# Double.net
KiCad netlist of a schematic drawn in EAGLE
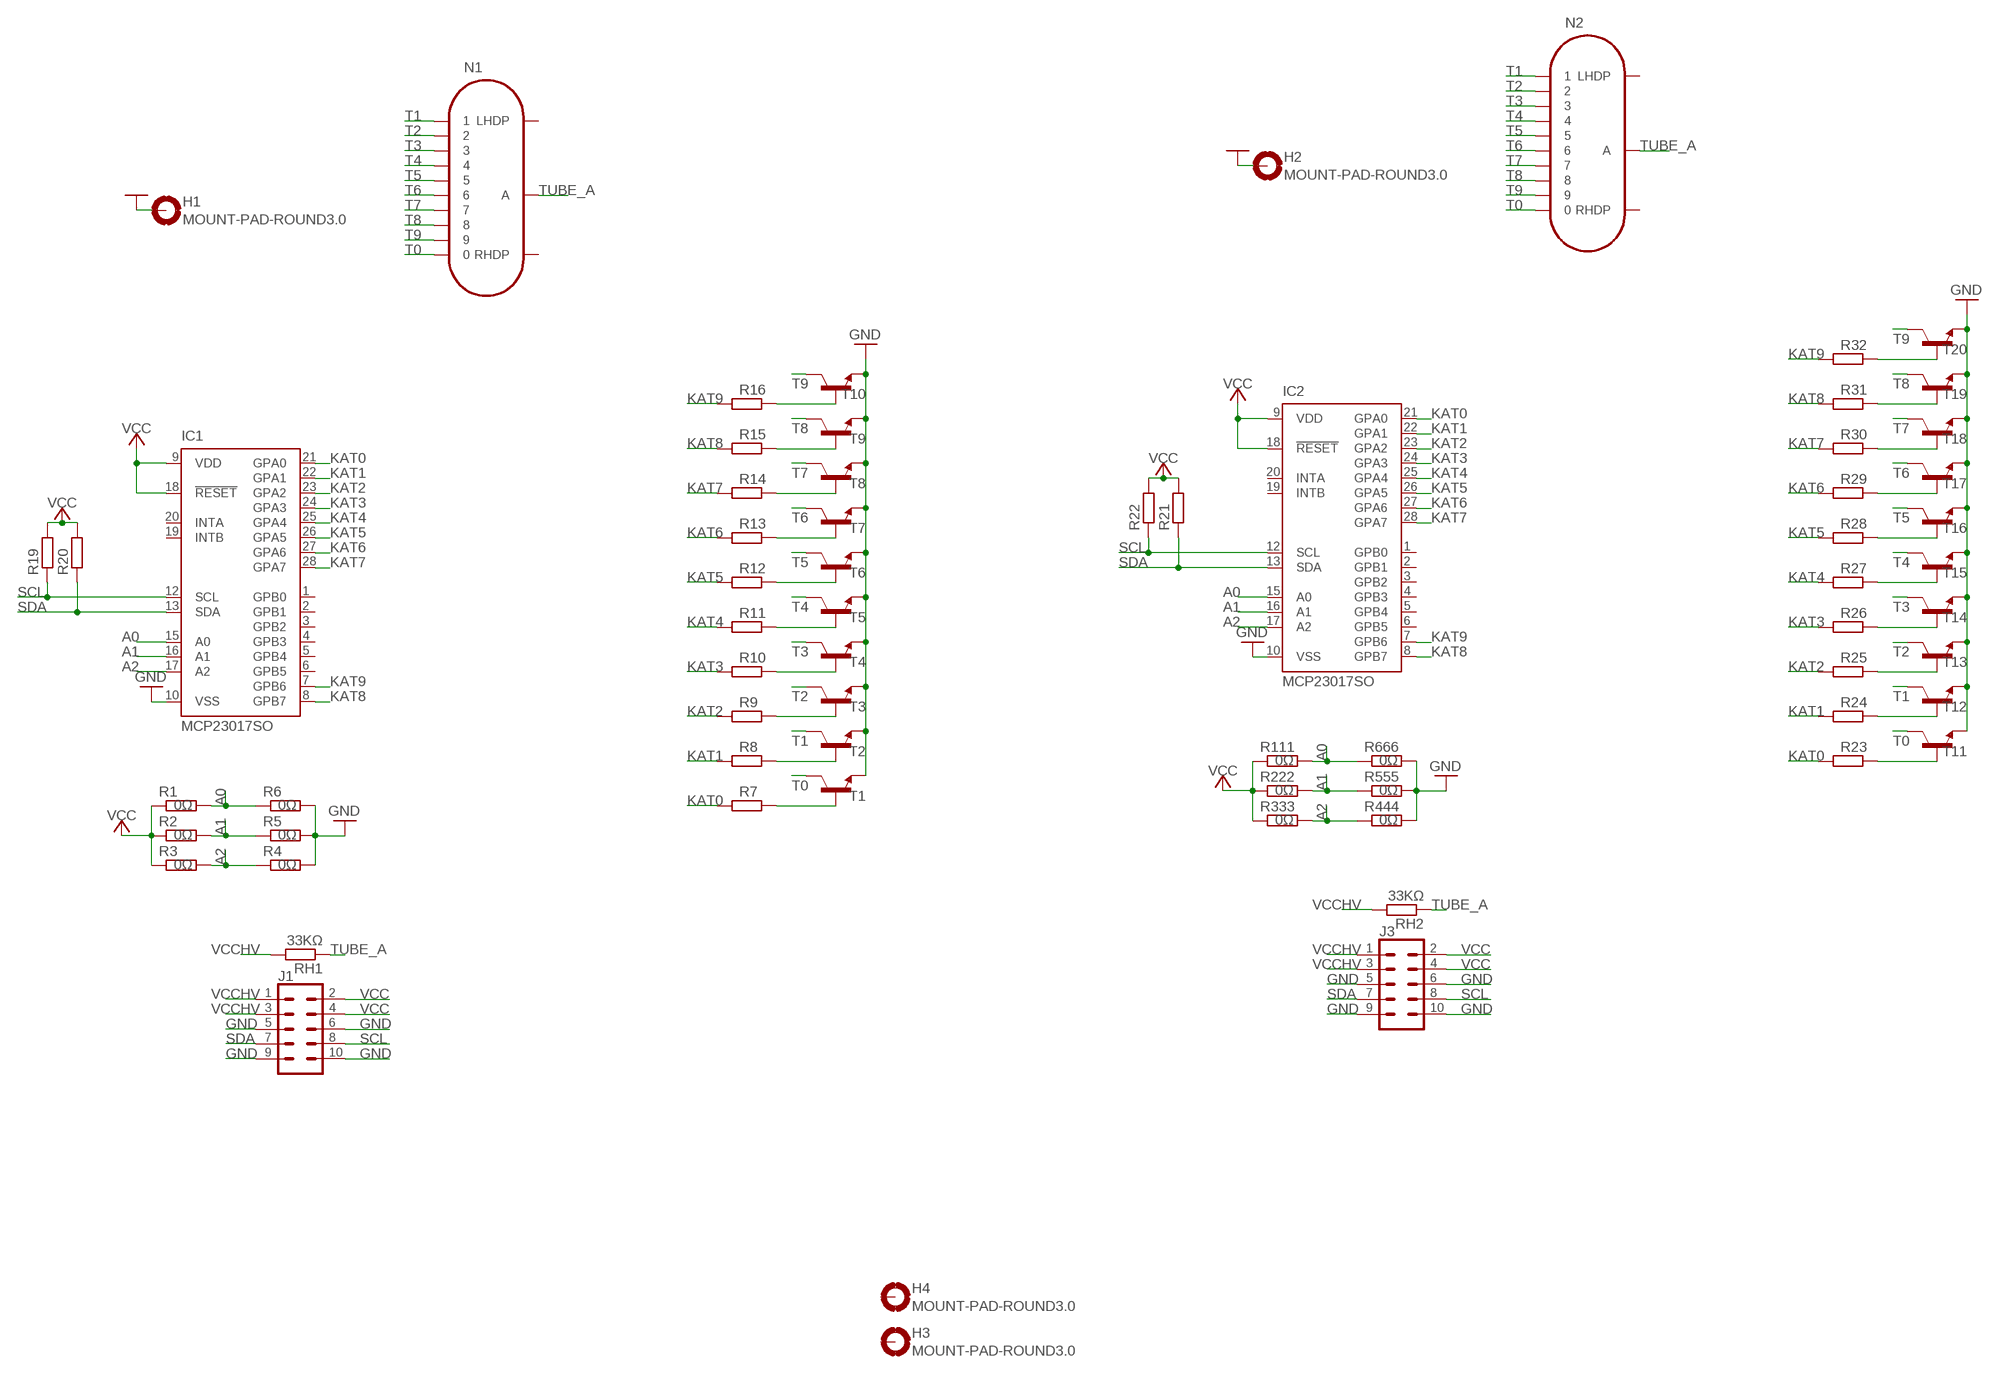
[diagram p0: schematic, sheet 1]

(export (version "E")
  (design (tool "Eeschema 10.0.6"))
  (components
    (comp (ref "H1")
      (value "MOUNT-PAD-ROUND3.0")
      (footprint "eagle-import:3,0-PAD")
      (libsource (lib "eagle-import") (part "MOUNT-PAD-ROUND3.0"))
    )
    (comp (ref "H2")
      (value "MOUNT-PAD-ROUND3.0")
      (footprint "eagle-import:3,0-PAD")
      (libsource (lib "eagle-import") (part "MOUNT-PAD-ROUND3.0"))
    )
    (comp (ref "H3")
      (value "MOUNT-PAD-ROUND3.0")
      (footprint "eagle-import:3,0-PAD")
      (libsource (lib "eagle-import") (part "MOUNT-PAD-ROUND3.0"))
    )
    (comp (ref "H4")
      (value "MOUNT-PAD-ROUND3.0")
      (footprint "eagle-import:3,0-PAD")
      (libsource (lib "eagle-import") (part "MOUNT-PAD-ROUND3.0"))
    )
    (comp (ref "IC1")
      (value "MCP23017SO")
      (footprint "eagle-import:SO28W")
      (libsource (lib "eagle-import") (part "MCP23017SO"))
    )
    (comp (ref "IC2")
      (value "MCP23017SO")
      (footprint "eagle-import:SO28W")
      (libsource (lib "eagle-import") (part "MCP23017SO"))
    )
    (comp (ref "J1")
      (value "CONN_05X2PTH")
      (footprint "eagle-import:2X5")
      (libsource (lib "eagle-import") (part "CONN_05X2PTH"))
    )
    (comp (ref "J3")
      (value "CONN_05X2PTH")
      (footprint "eagle-import:2X5")
      (libsource (lib "eagle-import") (part "CONN_05X2PTH"))
    )
    (comp (ref "N1")
      (value "IN-14")
      (footprint "eagle-import:IN-14")
      (libsource (lib "eagle-import") (part "IN-14"))
    )
    (comp (ref "N2")
      (value "IN-14")
      (footprint "eagle-import:IN-14")
      (libsource (lib "eagle-import") (part "IN-14"))
    )
    (comp (ref "R1")
      (value "0Ω")
      (footprint "eagle-import:R1206")
      (libsource (lib "eagle-import") (part "R-EU_R1206"))
    )
    (comp (ref "R2")
      (value "0Ω")
      (footprint "eagle-import:R1206")
      (libsource (lib "eagle-import") (part "R-EU_R1206"))
    )
    (comp (ref "R3")
      (value "0Ω")
      (footprint "eagle-import:R1206")
      (libsource (lib "eagle-import") (part "R-EU_R1206"))
    )
    (comp (ref "R4")
      (value "0Ω")
      (footprint "eagle-import:R1206")
      (libsource (lib "eagle-import") (part "R-EU_R1206"))
    )
    (comp (ref "R5")
      (value "0Ω")
      (footprint "eagle-import:R1206")
      (libsource (lib "eagle-import") (part "R-EU_R1206"))
    )
    (comp (ref "R6")
      (value "0Ω")
      (footprint "eagle-import:R1206")
      (libsource (lib "eagle-import") (part "R-EU_R1206"))
    )
    (comp (ref "R7")
      (value "R-EU_R1206")
      (footprint "eagle-import:R1206")
      (libsource (lib "eagle-import") (part "R-EU_R1206"))
    )
    (comp (ref "R8")
      (value "R-EU_R1206")
      (footprint "eagle-import:R1206")
      (libsource (lib "eagle-import") (part "R-EU_R1206"))
    )
    (comp (ref "R9")
      (value "R-EU_R1206")
      (footprint "eagle-import:R1206")
      (libsource (lib "eagle-import") (part "R-EU_R1206"))
    )
    (comp (ref "R10")
      (value "R-EU_R1206")
      (footprint "eagle-import:R1206")
      (libsource (lib "eagle-import") (part "R-EU_R1206"))
    )
    (comp (ref "R11")
      (value "R-EU_R1206")
      (footprint "eagle-import:R1206")
      (libsource (lib "eagle-import") (part "R-EU_R1206"))
    )
    (comp (ref "R12")
      (value "R-EU_R1206")
      (footprint "eagle-import:R1206")
      (libsource (lib "eagle-import") (part "R-EU_R1206"))
    )
    (comp (ref "R13")
      (value "R-EU_R1206")
      (footprint "eagle-import:R1206")
      (libsource (lib "eagle-import") (part "R-EU_R1206"))
    )
    (comp (ref "R14")
      (value "R-EU_R1206")
      (footprint "eagle-import:R1206")
      (libsource (lib "eagle-import") (part "R-EU_R1206"))
    )
    (comp (ref "R15")
      (value "R-EU_R1206")
      (footprint "eagle-import:R1206")
      (libsource (lib "eagle-import") (part "R-EU_R1206"))
    )
    (comp (ref "R16")
      (value "R-EU_R1206")
      (footprint "eagle-import:R1206")
      (libsource (lib "eagle-import") (part "R-EU_R1206"))
    )
    (comp (ref "R19")
      (value "R-EU_R1206")
      (footprint "eagle-import:R1206")
      (libsource (lib "eagle-import") (part "R-EU_R1206"))
    )
    (comp (ref "R20")
      (value "R-EU_R1206")
      (footprint "eagle-import:R1206")
      (libsource (lib "eagle-import") (part "R-EU_R1206"))
    )
    (comp (ref "R21")
      (value "R-EU_R1206")
      (footprint "eagle-import:R1206")
      (libsource (lib "eagle-import") (part "R-EU_R1206"))
    )
    (comp (ref "R22")
      (value "R-EU_R1206")
      (footprint "eagle-import:R1206")
      (libsource (lib "eagle-import") (part "R-EU_R1206"))
    )
    (comp (ref "R23")
      (value "R-EU_R1206")
      (footprint "eagle-import:R1206")
      (libsource (lib "eagle-import") (part "R-EU_R1206"))
    )
    (comp (ref "R24")
      (value "R-EU_R1206")
      (footprint "eagle-import:R1206")
      (libsource (lib "eagle-import") (part "R-EU_R1206"))
    )
    (comp (ref "R25")
      (value "R-EU_R1206")
      (footprint "eagle-import:R1206")
      (libsource (lib "eagle-import") (part "R-EU_R1206"))
    )
    (comp (ref "R26")
      (value "R-EU_R1206")
      (footprint "eagle-import:R1206")
      (libsource (lib "eagle-import") (part "R-EU_R1206"))
    )
    (comp (ref "R27")
      (value "R-EU_R1206")
      (footprint "eagle-import:R1206")
      (libsource (lib "eagle-import") (part "R-EU_R1206"))
    )
    (comp (ref "R28")
      (value "R-EU_R1206")
      (footprint "eagle-import:R1206")
      (libsource (lib "eagle-import") (part "R-EU_R1206"))
    )
    (comp (ref "R29")
      (value "R-EU_R1206")
      (footprint "eagle-import:R1206")
      (libsource (lib "eagle-import") (part "R-EU_R1206"))
    )
    (comp (ref "R30")
      (value "R-EU_R1206")
      (footprint "eagle-import:R1206")
      (libsource (lib "eagle-import") (part "R-EU_R1206"))
    )
    (comp (ref "R31")
      (value "R-EU_R1206")
      (footprint "eagle-import:R1206")
      (libsource (lib "eagle-import") (part "R-EU_R1206"))
    )
    (comp (ref "R32")
      (value "R-EU_R1206")
      (footprint "eagle-import:R1206")
      (libsource (lib "eagle-import") (part "R-EU_R1206"))
    )
    (comp (ref "R111")
      (value "0Ω")
      (footprint "eagle-import:R1206")
      (libsource (lib "eagle-import") (part "R-EU_R1206"))
    )
    (comp (ref "R222")
      (value "0Ω")
      (footprint "eagle-import:R1206")
      (libsource (lib "eagle-import") (part "R-EU_R1206"))
    )
    (comp (ref "R333")
      (value "0Ω")
      (footprint "eagle-import:R1206")
      (libsource (lib "eagle-import") (part "R-EU_R1206"))
    )
    (comp (ref "R444")
      (value "0Ω")
      (footprint "eagle-import:R1206")
      (libsource (lib "eagle-import") (part "R-EU_R1206"))
    )
    (comp (ref "R555")
      (value "0Ω")
      (footprint "eagle-import:R1206")
      (libsource (lib "eagle-import") (part "R-EU_R1206"))
    )
    (comp (ref "R666")
      (value "0Ω")
      (footprint "eagle-import:R1206")
      (libsource (lib "eagle-import") (part "R-EU_R1206"))
    )
    (comp (ref "RH1")
      (value "33KΩ")
      (footprint "eagle-import:0207_15")
      (libsource (lib "eagle-import") (part "R-EU_0207/15"))
    )
    (comp (ref "RH2")
      (value "33KΩ")
      (footprint "eagle-import:0207_15")
      (libsource (lib "eagle-import") (part "R-EU_0207/15"))
    )
    (comp (ref "T1")
      (value "MMBTA42LT1-NPN-SOT23-BEC")
      (footprint "eagle-import:SOT23-BEC")
      (libsource (lib "eagle-import") (part "-NPN-SOT23-BECMMBTA42LT1"))
    )
    (comp (ref "T2")
      (value "MMBTA42LT1-NPN-SOT23-BEC")
      (footprint "eagle-import:SOT23-BEC")
      (libsource (lib "eagle-import") (part "-NPN-SOT23-BECMMBTA42LT1"))
    )
    (comp (ref "T3")
      (value "MMBTA42LT1-NPN-SOT23-BEC")
      (footprint "eagle-import:SOT23-BEC")
      (libsource (lib "eagle-import") (part "-NPN-SOT23-BECMMBTA42LT1"))
    )
    (comp (ref "T4")
      (value "MMBTA42LT1-NPN-SOT23-BEC")
      (footprint "eagle-import:SOT23-BEC")
      (libsource (lib "eagle-import") (part "-NPN-SOT23-BECMMBTA42LT1"))
    )
    (comp (ref "T5")
      (value "MMBTA42LT1-NPN-SOT23-BEC")
      (footprint "eagle-import:SOT23-BEC")
      (libsource (lib "eagle-import") (part "-NPN-SOT23-BECMMBTA42LT1"))
    )
    (comp (ref "T6")
      (value "MMBTA42LT1-NPN-SOT23-BEC")
      (footprint "eagle-import:SOT23-BEC")
      (libsource (lib "eagle-import") (part "-NPN-SOT23-BECMMBTA42LT1"))
    )
    (comp (ref "T7")
      (value "MMBTA42LT1-NPN-SOT23-BEC")
      (footprint "eagle-import:SOT23-BEC")
      (libsource (lib "eagle-import") (part "-NPN-SOT23-BECMMBTA42LT1"))
    )
    (comp (ref "T8")
      (value "MMBTA42LT1-NPN-SOT23-BEC")
      (footprint "eagle-import:SOT23-BEC")
      (libsource (lib "eagle-import") (part "-NPN-SOT23-BECMMBTA42LT1"))
    )
    (comp (ref "T9")
      (value "MMBTA42LT1-NPN-SOT23-BEC")
      (footprint "eagle-import:SOT23-BEC")
      (libsource (lib "eagle-import") (part "-NPN-SOT23-BECMMBTA42LT1"))
    )
    (comp (ref "T10")
      (value "MMBTA42LT1-NPN-SOT23-BEC")
      (footprint "eagle-import:SOT23-BEC")
      (libsource (lib "eagle-import") (part "-NPN-SOT23-BECMMBTA42LT1"))
    )
    (comp (ref "T11")
      (value "MMBTA42LT1-NPN-SOT23-BEC")
      (footprint "eagle-import:SOT23-BEC")
      (libsource (lib "eagle-import") (part "-NPN-SOT23-BECMMBTA42LT1"))
    )
    (comp (ref "T12")
      (value "MMBTA42LT1-NPN-SOT23-BEC")
      (footprint "eagle-import:SOT23-BEC")
      (libsource (lib "eagle-import") (part "-NPN-SOT23-BECMMBTA42LT1"))
    )
    (comp (ref "T13")
      (value "MMBTA42LT1-NPN-SOT23-BEC")
      (footprint "eagle-import:SOT23-BEC")
      (libsource (lib "eagle-import") (part "-NPN-SOT23-BECMMBTA42LT1"))
    )
    (comp (ref "T14")
      (value "MMBTA42LT1-NPN-SOT23-BEC")
      (footprint "eagle-import:SOT23-BEC")
      (libsource (lib "eagle-import") (part "-NPN-SOT23-BECMMBTA42LT1"))
    )
    (comp (ref "T15")
      (value "MMBTA42LT1-NPN-SOT23-BEC")
      (footprint "eagle-import:SOT23-BEC")
      (libsource (lib "eagle-import") (part "-NPN-SOT23-BECMMBTA42LT1"))
    )
    (comp (ref "T16")
      (value "MMBTA42LT1-NPN-SOT23-BEC")
      (footprint "eagle-import:SOT23-BEC")
      (libsource (lib "eagle-import") (part "-NPN-SOT23-BECMMBTA42LT1"))
    )
    (comp (ref "T17")
      (value "MMBTA42LT1-NPN-SOT23-BEC")
      (footprint "eagle-import:SOT23-BEC")
      (libsource (lib "eagle-import") (part "-NPN-SOT23-BECMMBTA42LT1"))
    )
    (comp (ref "T18")
      (value "MMBTA42LT1-NPN-SOT23-BEC")
      (footprint "eagle-import:SOT23-BEC")
      (libsource (lib "eagle-import") (part "-NPN-SOT23-BECMMBTA42LT1"))
    )
    (comp (ref "T19")
      (value "MMBTA42LT1-NPN-SOT23-BEC")
      (footprint "eagle-import:SOT23-BEC")
      (libsource (lib "eagle-import") (part "-NPN-SOT23-BECMMBTA42LT1"))
    )
    (comp (ref "T20")
      (value "MMBTA42LT1-NPN-SOT23-BEC")
      (footprint "eagle-import:SOT23-BEC")
      (libsource (lib "eagle-import") (part "-NPN-SOT23-BECMMBTA42LT1"))
    )
  )
  (nets
    (net (code "1") (name "/A0") (class "Default")
      (node (ref "IC1") (pin "15") (pinfunction "A0_15") (pintype "input"))
      (node (ref "IC2") (pin "15") (pinfunction "A0_15") (pintype "input"))
      (node (ref "R1") (pin "2") (pinfunction "2_2") (pintype "passive"))
      (node (ref "R111") (pin "2") (pinfunction "2_2") (pintype "passive"))
      (node (ref "R6") (pin "1") (pinfunction "1_1") (pintype "passive"))
      (node (ref "R666") (pin "1") (pinfunction "1_1") (pintype "passive"))
    )
    (net (code "2") (name "/A1") (class "Default")
      (node (ref "IC1") (pin "16") (pinfunction "A1_16") (pintype "input"))
      (node (ref "IC2") (pin "16") (pinfunction "A1_16") (pintype "input"))
      (node (ref "R2") (pin "2") (pinfunction "2_2") (pintype "passive"))
      (node (ref "R222") (pin "2") (pinfunction "2_2") (pintype "passive"))
      (node (ref "R5") (pin "1") (pinfunction "1_1") (pintype "passive"))
      (node (ref "R555") (pin "1") (pinfunction "1_1") (pintype "passive"))
    )
    (net (code "3") (name "/A2") (class "Default")
      (node (ref "IC1") (pin "17") (pinfunction "A2_17") (pintype "input"))
      (node (ref "IC2") (pin "17") (pinfunction "A2_17") (pintype "input"))
      (node (ref "R3") (pin "2") (pinfunction "2_2") (pintype "passive"))
      (node (ref "R333") (pin "2") (pinfunction "2_2") (pintype "passive"))
      (node (ref "R4") (pin "1") (pinfunction "1_1") (pintype "passive"))
      (node (ref "R444") (pin "1") (pinfunction "1_1") (pintype "passive"))
    )
    (net (code "4") (name "/KAT0") (class "Default")
      (node (ref "IC1") (pin "21") (pinfunction "GPA0_21") (pintype "bidirectional"))
      (node (ref "IC2") (pin "21") (pinfunction "GPA0_21") (pintype "bidirectional"))
      (node (ref "R23") (pin "1") (pinfunction "1_1") (pintype "passive"))
      (node (ref "R7") (pin "1") (pinfunction "1_1") (pintype "passive"))
    )
    (net (code "5") (name "/KAT1") (class "Default")
      (node (ref "IC1") (pin "22") (pinfunction "GPA1_22") (pintype "bidirectional"))
      (node (ref "IC2") (pin "22") (pinfunction "GPA1_22") (pintype "bidirectional"))
      (node (ref "R24") (pin "1") (pinfunction "1_1") (pintype "passive"))
      (node (ref "R8") (pin "1") (pinfunction "1_1") (pintype "passive"))
    )
    (net (code "6") (name "/KAT2") (class "Default")
      (node (ref "IC1") (pin "23") (pinfunction "GPA2_23") (pintype "bidirectional"))
      (node (ref "IC2") (pin "23") (pinfunction "GPA2_23") (pintype "bidirectional"))
      (node (ref "R25") (pin "1") (pinfunction "1_1") (pintype "passive"))
      (node (ref "R9") (pin "1") (pinfunction "1_1") (pintype "passive"))
    )
    (net (code "7") (name "/KAT3") (class "Default")
      (node (ref "IC1") (pin "24") (pinfunction "GPA3_24") (pintype "bidirectional"))
      (node (ref "IC2") (pin "24") (pinfunction "GPA3_24") (pintype "bidirectional"))
      (node (ref "R10") (pin "1") (pinfunction "1_1") (pintype "passive"))
      (node (ref "R26") (pin "1") (pinfunction "1_1") (pintype "passive"))
    )
    (net (code "8") (name "/KAT4") (class "Default")
      (node (ref "IC1") (pin "25") (pinfunction "GPA4_25") (pintype "bidirectional"))
      (node (ref "IC2") (pin "25") (pinfunction "GPA4_25") (pintype "bidirectional"))
      (node (ref "R11") (pin "1") (pinfunction "1_1") (pintype "passive"))
      (node (ref "R27") (pin "1") (pinfunction "1_1") (pintype "passive"))
    )
    (net (code "9") (name "/KAT5") (class "Default")
      (node (ref "IC1") (pin "26") (pinfunction "GPA5_26") (pintype "bidirectional"))
      (node (ref "IC2") (pin "26") (pinfunction "GPA5_26") (pintype "bidirectional"))
      (node (ref "R12") (pin "1") (pinfunction "1_1") (pintype "passive"))
      (node (ref "R28") (pin "1") (pinfunction "1_1") (pintype "passive"))
    )
    (net (code "10") (name "/KAT6") (class "Default")
      (node (ref "IC1") (pin "27") (pinfunction "GPA6_27") (pintype "bidirectional"))
      (node (ref "IC2") (pin "27") (pinfunction "GPA6_27") (pintype "bidirectional"))
      (node (ref "R13") (pin "1") (pinfunction "1_1") (pintype "passive"))
      (node (ref "R29") (pin "1") (pinfunction "1_1") (pintype "passive"))
    )
    (net (code "11") (name "/KAT7") (class "Default")
      (node (ref "IC1") (pin "28") (pinfunction "GPA7_28") (pintype "bidirectional"))
      (node (ref "IC2") (pin "28") (pinfunction "GPA7_28") (pintype "bidirectional"))
      (node (ref "R14") (pin "1") (pinfunction "1_1") (pintype "passive"))
      (node (ref "R30") (pin "1") (pinfunction "1_1") (pintype "passive"))
    )
    (net (code "12") (name "/KAT8") (class "Default")
      (node (ref "IC1") (pin "8") (pinfunction "GPB7_8") (pintype "bidirectional"))
      (node (ref "IC2") (pin "8") (pinfunction "GPB7_8") (pintype "bidirectional"))
      (node (ref "R15") (pin "1") (pinfunction "1_1") (pintype "passive"))
      (node (ref "R31") (pin "1") (pinfunction "1_1") (pintype "passive"))
    )
    (net (code "13") (name "/KAT9") (class "Default")
      (node (ref "IC1") (pin "7") (pinfunction "GPB6_7") (pintype "bidirectional"))
      (node (ref "IC2") (pin "7") (pinfunction "GPB6_7") (pintype "bidirectional"))
      (node (ref "R16") (pin "1") (pinfunction "1_1") (pintype "passive"))
      (node (ref "R32") (pin "1") (pinfunction "1_1") (pintype "passive"))
    )
    (net (code "14") (name "/SCL") (class "Default")
      (node (ref "IC1") (pin "12") (pinfunction "SCL_12") (pintype "input"))
      (node (ref "IC2") (pin "12") (pinfunction "SCL_12") (pintype "input"))
      (node (ref "J1") (pin "8") (pinfunction "8_8") (pintype "passive"))
      (node (ref "J3") (pin "8") (pinfunction "8_8") (pintype "passive"))
      (node (ref "R19") (pin "1") (pinfunction "1_1") (pintype "passive"))
      (node (ref "R22") (pin "1") (pinfunction "1_1") (pintype "passive"))
    )
    (net (code "15") (name "/SDA") (class "Default")
      (node (ref "IC1") (pin "13") (pinfunction "SDA_13") (pintype "bidirectional"))
      (node (ref "IC2") (pin "13") (pinfunction "SDA_13") (pintype "bidirectional"))
      (node (ref "J1") (pin "7") (pinfunction "7_7") (pintype "passive"))
      (node (ref "J3") (pin "7") (pinfunction "7_7") (pintype "passive"))
      (node (ref "R20") (pin "1") (pinfunction "1_1") (pintype "passive"))
      (node (ref "R21") (pin "1") (pinfunction "1_1") (pintype "passive"))
    )
    (net (code "16") (name "/T0") (class "Default")
      (node (ref "N1") (pin "0") (pinfunction "0_0") (pintype "bidirectional"))
      (node (ref "N2") (pin "0") (pinfunction "0_0") (pintype "bidirectional"))
      (node (ref "T1") (pin "C") (pinfunction "C_C") (pintype "passive"))
      (node (ref "T11") (pin "C") (pinfunction "C_C") (pintype "passive"))
    )
    (net (code "17") (name "/T1") (class "Default")
      (node (ref "N1") (pin "1") (pinfunction "1_1") (pintype "bidirectional"))
      (node (ref "N2") (pin "1") (pinfunction "1_1") (pintype "bidirectional"))
      (node (ref "T12") (pin "C") (pinfunction "C_C") (pintype "passive"))
      (node (ref "T2") (pin "C") (pinfunction "C_C") (pintype "passive"))
    )
    (net (code "18") (name "/T2") (class "Default")
      (node (ref "N1") (pin "2") (pinfunction "2_2") (pintype "bidirectional"))
      (node (ref "N2") (pin "2") (pinfunction "2_2") (pintype "bidirectional"))
      (node (ref "T13") (pin "C") (pinfunction "C_C") (pintype "passive"))
      (node (ref "T3") (pin "C") (pinfunction "C_C") (pintype "passive"))
    )
    (net (code "19") (name "/T3") (class "Default")
      (node (ref "N1") (pin "3") (pinfunction "3_3") (pintype "bidirectional"))
      (node (ref "N2") (pin "3") (pinfunction "3_3") (pintype "bidirectional"))
      (node (ref "T14") (pin "C") (pinfunction "C_C") (pintype "passive"))
      (node (ref "T4") (pin "C") (pinfunction "C_C") (pintype "passive"))
    )
    (net (code "20") (name "/T4") (class "Default")
      (node (ref "N1") (pin "4") (pinfunction "4_4") (pintype "bidirectional"))
      (node (ref "N2") (pin "4") (pinfunction "4_4") (pintype "bidirectional"))
      (node (ref "T15") (pin "C") (pinfunction "C_C") (pintype "passive"))
      (node (ref "T5") (pin "C") (pinfunction "C_C") (pintype "passive"))
    )
    (net (code "21") (name "/T5") (class "Default")
      (node (ref "N1") (pin "5") (pinfunction "5_5") (pintype "bidirectional"))
      (node (ref "N2") (pin "5") (pinfunction "5_5") (pintype "bidirectional"))
      (node (ref "T16") (pin "C") (pinfunction "C_C") (pintype "passive"))
      (node (ref "T6") (pin "C") (pinfunction "C_C") (pintype "passive"))
    )
    (net (code "22") (name "/T6") (class "Default")
      (node (ref "N1") (pin "6") (pinfunction "6_6") (pintype "bidirectional"))
      (node (ref "N2") (pin "6") (pinfunction "6_6") (pintype "bidirectional"))
      (node (ref "T17") (pin "C") (pinfunction "C_C") (pintype "passive"))
      (node (ref "T7") (pin "C") (pinfunction "C_C") (pintype "passive"))
    )
    (net (code "23") (name "/T7") (class "Default")
      (node (ref "N1") (pin "7") (pinfunction "7_7") (pintype "bidirectional"))
      (node (ref "N2") (pin "7") (pinfunction "7_7") (pintype "bidirectional"))
      (node (ref "T18") (pin "C") (pinfunction "C_C") (pintype "passive"))
      (node (ref "T8") (pin "C") (pinfunction "C_C") (pintype "passive"))
    )
    (net (code "24") (name "/T8") (class "Default")
      (node (ref "N1") (pin "8") (pinfunction "8_8") (pintype "bidirectional"))
      (node (ref "N2") (pin "8") (pinfunction "8_8") (pintype "bidirectional"))
      (node (ref "T19") (pin "C") (pinfunction "C_C") (pintype "passive"))
      (node (ref "T9") (pin "C") (pinfunction "C_C") (pintype "passive"))
    )
    (net (code "25") (name "/T9") (class "Default")
      (node (ref "N1") (pin "9") (pinfunction "9_9") (pintype "bidirectional"))
      (node (ref "N2") (pin "9") (pinfunction "9_9") (pintype "bidirectional"))
      (node (ref "T10") (pin "C") (pinfunction "C_C") (pintype "passive"))
      (node (ref "T20") (pin "C") (pinfunction "C_C") (pintype "passive"))
    )
    (net (code "26") (name "/TUBE_A") (class "Default")
      (node (ref "N1") (pin "A") (pinfunction "A_A") (pintype "bidirectional"))
      (node (ref "N2") (pin "A") (pinfunction "A_A") (pintype "bidirectional"))
      (node (ref "RH1") (pin "1") (pinfunction "1_1") (pintype "passive"))
      (node (ref "RH2") (pin "1") (pinfunction "1_1") (pintype "passive"))
    )
    (net (code "27") (name "/VCCHV") (class "Default")
      (node (ref "J1") (pin "1") (pinfunction "1_1") (pintype "passive"))
      (node (ref "J1") (pin "3") (pinfunction "3_3") (pintype "passive"))
      (node (ref "J3") (pin "1") (pinfunction "1_1") (pintype "passive"))
      (node (ref "J3") (pin "3") (pinfunction "3_3") (pintype "passive"))
      (node (ref "RH1") (pin "2") (pinfunction "2_2") (pintype "passive"))
      (node (ref "RH2") (pin "2") (pinfunction "2_2") (pintype "passive"))
    )
    (net (code "28") (name "GND") (class "Default")
      (node (ref "H1") (pin "B3,0") (pinfunction "MOUNT_B3,0") (pintype "passive"))
      (node (ref "H2") (pin "B3,0") (pinfunction "MOUNT_B3,0") (pintype "passive"))
      (node (ref "IC1") (pin "10") (pinfunction "VSS_10") (pintype "power_in"))
      (node (ref "IC2") (pin "10") (pinfunction "VSS_10") (pintype "power_in"))
      (node (ref "J1") (pin "10") (pinfunction "10_10") (pintype "passive"))
      (node (ref "J1") (pin "5") (pinfunction "5_5") (pintype "passive"))
      (node (ref "J1") (pin "6") (pinfunction "6_6") (pintype "passive"))
      (node (ref "J1") (pin "9") (pinfunction "9_9") (pintype "passive"))
      (node (ref "J3") (pin "10") (pinfunction "10_10") (pintype "passive"))
      (node (ref "J3") (pin "5") (pinfunction "5_5") (pintype "passive"))
      (node (ref "J3") (pin "6") (pinfunction "6_6") (pintype "passive"))
      (node (ref "J3") (pin "9") (pinfunction "9_9") (pintype "passive"))
      (node (ref "R4") (pin "2") (pinfunction "2_2") (pintype "passive"))
      (node (ref "R444") (pin "2") (pinfunction "2_2") (pintype "passive"))
      (node (ref "R5") (pin "2") (pinfunction "2_2") (pintype "passive"))
      (node (ref "R555") (pin "2") (pinfunction "2_2") (pintype "passive"))
      (node (ref "R6") (pin "2") (pinfunction "2_2") (pintype "passive"))
      (node (ref "R666") (pin "2") (pinfunction "2_2") (pintype "passive"))
      (node (ref "T1") (pin "E") (pinfunction "E_E") (pintype "passive"))
      (node (ref "T10") (pin "E") (pinfunction "E_E") (pintype "passive"))
      (node (ref "T11") (pin "E") (pinfunction "E_E") (pintype "passive"))
      (node (ref "T12") (pin "E") (pinfunction "E_E") (pintype "passive"))
      (node (ref "T13") (pin "E") (pinfunction "E_E") (pintype "passive"))
      (node (ref "T14") (pin "E") (pinfunction "E_E") (pintype "passive"))
      (node (ref "T15") (pin "E") (pinfunction "E_E") (pintype "passive"))
      (node (ref "T16") (pin "E") (pinfunction "E_E") (pintype "passive"))
      (node (ref "T17") (pin "E") (pinfunction "E_E") (pintype "passive"))
      (node (ref "T18") (pin "E") (pinfunction "E_E") (pintype "passive"))
      (node (ref "T19") (pin "E") (pinfunction "E_E") (pintype "passive"))
      (node (ref "T2") (pin "E") (pinfunction "E_E") (pintype "passive"))
      (node (ref "T20") (pin "E") (pinfunction "E_E") (pintype "passive"))
      (node (ref "T3") (pin "E") (pinfunction "E_E") (pintype "passive"))
      (node (ref "T4") (pin "E") (pinfunction "E_E") (pintype "passive"))
      (node (ref "T5") (pin "E") (pinfunction "E_E") (pintype "passive"))
      (node (ref "T6") (pin "E") (pinfunction "E_E") (pintype "passive"))
      (node (ref "T7") (pin "E") (pinfunction "E_E") (pintype "passive"))
      (node (ref "T8") (pin "E") (pinfunction "E_E") (pintype "passive"))
      (node (ref "T9") (pin "E") (pinfunction "E_E") (pintype "passive"))
    )
    (net (code "29") (name "Net-(R7-Pad2)") (class "Default")
      (node (ref "R7") (pin "2") (pinfunction "2_2") (pintype "passive"))
      (node (ref "T1") (pin "B") (pinfunction "B_B") (pintype "passive"))
    )
    (net (code "30") (name "Net-(R8-Pad2)") (class "Default")
      (node (ref "R8") (pin "2") (pinfunction "2_2") (pintype "passive"))
      (node (ref "T2") (pin "B") (pinfunction "B_B") (pintype "passive"))
    )
    (net (code "31") (name "Net-(R9-Pad2)") (class "Default")
      (node (ref "R9") (pin "2") (pinfunction "2_2") (pintype "passive"))
      (node (ref "T3") (pin "B") (pinfunction "B_B") (pintype "passive"))
    )
    (net (code "32") (name "Net-(R10-Pad2)") (class "Default")
      (node (ref "R10") (pin "2") (pinfunction "2_2") (pintype "passive"))
      (node (ref "T4") (pin "B") (pinfunction "B_B") (pintype "passive"))
    )
    (net (code "33") (name "Net-(R11-Pad2)") (class "Default")
      (node (ref "R11") (pin "2") (pinfunction "2_2") (pintype "passive"))
      (node (ref "T5") (pin "B") (pinfunction "B_B") (pintype "passive"))
    )
    (net (code "34") (name "Net-(R12-Pad2)") (class "Default")
      (node (ref "R12") (pin "2") (pinfunction "2_2") (pintype "passive"))
      (node (ref "T6") (pin "B") (pinfunction "B_B") (pintype "passive"))
    )
    (net (code "35") (name "Net-(R13-Pad2)") (class "Default")
      (node (ref "R13") (pin "2") (pinfunction "2_2") (pintype "passive"))
      (node (ref "T7") (pin "B") (pinfunction "B_B") (pintype "passive"))
    )
    (net (code "36") (name "Net-(R14-Pad2)") (class "Default")
      (node (ref "R14") (pin "2") (pinfunction "2_2") (pintype "passive"))
      (node (ref "T8") (pin "B") (pinfunction "B_B") (pintype "passive"))
    )
    (net (code "37") (name "Net-(R15-Pad2)") (class "Default")
      (node (ref "R15") (pin "2") (pinfunction "2_2") (pintype "passive"))
      (node (ref "T9") (pin "B") (pinfunction "B_B") (pintype "passive"))
    )
    (net (code "38") (name "Net-(R16-Pad2)") (class "Default")
      (node (ref "R16") (pin "2") (pinfunction "2_2") (pintype "passive"))
      (node (ref "T10") (pin "B") (pinfunction "B_B") (pintype "passive"))
    )
    (net (code "39") (name "Net-(R23-Pad2)") (class "Default")
      (node (ref "R23") (pin "2") (pinfunction "2_2") (pintype "passive"))
      (node (ref "T11") (pin "B") (pinfunction "B_B") (pintype "passive"))
    )
    (net (code "40") (name "Net-(R24-Pad2)") (class "Default")
      (node (ref "R24") (pin "2") (pinfunction "2_2") (pintype "passive"))
      (node (ref "T12") (pin "B") (pinfunction "B_B") (pintype "passive"))
    )
    (net (code "41") (name "Net-(R25-Pad2)") (class "Default")
      (node (ref "R25") (pin "2") (pinfunction "2_2") (pintype "passive"))
      (node (ref "T13") (pin "B") (pinfunction "B_B") (pintype "passive"))
    )
    (net (code "42") (name "Net-(R26-Pad2)") (class "Default")
      (node (ref "R26") (pin "2") (pinfunction "2_2") (pintype "passive"))
      (node (ref "T14") (pin "B") (pinfunction "B_B") (pintype "passive"))
    )
    (net (code "43") (name "Net-(R27-Pad2)") (class "Default")
      (node (ref "R27") (pin "2") (pinfunction "2_2") (pintype "passive"))
      (node (ref "T15") (pin "B") (pinfunction "B_B") (pintype "passive"))
    )
    (net (code "44") (name "Net-(R28-Pad2)") (class "Default")
      (node (ref "R28") (pin "2") (pinfunction "2_2") (pintype "passive"))
      (node (ref "T16") (pin "B") (pinfunction "B_B") (pintype "passive"))
    )
    (net (code "45") (name "Net-(R29-Pad2)") (class "Default")
      (node (ref "R29") (pin "2") (pinfunction "2_2") (pintype "passive"))
      (node (ref "T17") (pin "B") (pinfunction "B_B") (pintype "passive"))
    )
    (net (code "46") (name "Net-(R30-Pad2)") (class "Default")
      (node (ref "R30") (pin "2") (pinfunction "2_2") (pintype "passive"))
      (node (ref "T18") (pin "B") (pinfunction "B_B") (pintype "passive"))
    )
    (net (code "47") (name "Net-(R31-Pad2)") (class "Default")
      (node (ref "R31") (pin "2") (pinfunction "2_2") (pintype "passive"))
      (node (ref "T19") (pin "B") (pinfunction "B_B") (pintype "passive"))
    )
    (net (code "48") (name "Net-(R32-Pad2)") (class "Default")
      (node (ref "R32") (pin "2") (pinfunction "2_2") (pintype "passive"))
      (node (ref "T20") (pin "B") (pinfunction "B_B") (pintype "passive"))
    )
    (net (code "49") (name "VCC") (class "Default")
      (node (ref "IC1") (pin "18") (pinfunction "~{RESET}_18") (pintype "input"))
      (node (ref "IC1") (pin "9") (pinfunction "VDD_9") (pintype "power_in"))
      (node (ref "IC2") (pin "18") (pinfunction "~{RESET}_18") (pintype "input"))
      (node (ref "IC2") (pin "9") (pinfunction "VDD_9") (pintype "power_in"))
      (node (ref "J1") (pin "2") (pinfunction "2_2") (pintype "passive"))
      (node (ref "J1") (pin "4") (pinfunction "4_4") (pintype "passive"))
      (node (ref "J3") (pin "2") (pinfunction "2_2") (pintype "passive"))
      (node (ref "J3") (pin "4") (pinfunction "4_4") (pintype "passive"))
      (node (ref "R1") (pin "1") (pinfunction "1_1") (pintype "passive"))
      (node (ref "R111") (pin "1") (pinfunction "1_1") (pintype "passive"))
      (node (ref "R19") (pin "2") (pinfunction "2_2") (pintype "passive"))
      (node (ref "R2") (pin "1") (pinfunction "1_1") (pintype "passive"))
      (node (ref "R20") (pin "2") (pinfunction "2_2") (pintype "passive"))
      (node (ref "R21") (pin "2") (pinfunction "2_2") (pintype "passive"))
      (node (ref "R22") (pin "2") (pinfunction "2_2") (pintype "passive"))
      (node (ref "R222") (pin "1") (pinfunction "1_1") (pintype "passive"))
      (node (ref "R3") (pin "1") (pinfunction "1_1") (pintype "passive"))
      (node (ref "R333") (pin "1") (pinfunction "1_1") (pintype "passive"))
    )
    (net (code "50") (name "unconnected-(H3-MOUNT-PadB3,0)") (class "Default")
      (node (ref "H3") (pin "B3,0") (pinfunction "MOUNT_B3,0") (pintype "passive"))
    )
    (net (code "51") (name "unconnected-(H4-MOUNT-PadB3,0)") (class "Default")
      (node (ref "H4") (pin "B3,0") (pinfunction "MOUNT_B3,0") (pintype "passive"))
    )
    (net (code "52") (name "unconnected-(IC1-GPB0-Pad1)") (class "Default")
      (node (ref "IC1") (pin "1") (pinfunction "GPB0_1") (pintype "bidirectional"))
    )
    (net (code "53") (name "unconnected-(IC1-GPB1-Pad2)") (class "Default")
      (node (ref "IC1") (pin "2") (pinfunction "GPB1_2") (pintype "bidirectional"))
    )
    (net (code "54") (name "unconnected-(IC1-GPB2-Pad3)") (class "Default")
      (node (ref "IC1") (pin "3") (pinfunction "GPB2_3") (pintype "bidirectional"))
    )
    (net (code "55") (name "unconnected-(IC1-GPB3-Pad4)") (class "Default")
      (node (ref "IC1") (pin "4") (pinfunction "GPB3_4") (pintype "bidirectional"))
    )
    (net (code "56") (name "unconnected-(IC1-GPB4-Pad5)") (class "Default")
      (node (ref "IC1") (pin "5") (pinfunction "GPB4_5") (pintype "bidirectional"))
    )
    (net (code "57") (name "unconnected-(IC1-GPB5-Pad6)") (class "Default")
      (node (ref "IC1") (pin "6") (pinfunction "GPB5_6") (pintype "bidirectional"))
    )
    (net (code "58") (name "unconnected-(IC1-INTA-Pad20)") (class "Default")
      (node (ref "IC1") (pin "20") (pinfunction "INTA_20") (pintype "output"))
    )
    (net (code "59") (name "unconnected-(IC1-INTB-Pad19)") (class "Default")
      (node (ref "IC1") (pin "19") (pinfunction "INTB_19") (pintype "output"))
    )
    (net (code "60") (name "unconnected-(IC2-GPB0-Pad1)") (class "Default")
      (node (ref "IC2") (pin "1") (pinfunction "GPB0_1") (pintype "bidirectional"))
    )
    (net (code "61") (name "unconnected-(IC2-GPB1-Pad2)") (class "Default")
      (node (ref "IC2") (pin "2") (pinfunction "GPB1_2") (pintype "bidirectional"))
    )
    (net (code "62") (name "unconnected-(IC2-GPB2-Pad3)") (class "Default")
      (node (ref "IC2") (pin "3") (pinfunction "GPB2_3") (pintype "bidirectional"))
    )
    (net (code "63") (name "unconnected-(IC2-GPB3-Pad4)") (class "Default")
      (node (ref "IC2") (pin "4") (pinfunction "GPB3_4") (pintype "bidirectional"))
    )
    (net (code "64") (name "unconnected-(IC2-GPB4-Pad5)") (class "Default")
      (node (ref "IC2") (pin "5") (pinfunction "GPB4_5") (pintype "bidirectional"))
    )
    (net (code "65") (name "unconnected-(IC2-GPB5-Pad6)") (class "Default")
      (node (ref "IC2") (pin "6") (pinfunction "GPB5_6") (pintype "bidirectional"))
    )
    (net (code "66") (name "unconnected-(IC2-INTA-Pad20)") (class "Default")
      (node (ref "IC2") (pin "20") (pinfunction "INTA_20") (pintype "output"))
    )
    (net (code "67") (name "unconnected-(IC2-INTB-Pad19)") (class "Default")
      (node (ref "IC2") (pin "19") (pinfunction "INTB_19") (pintype "output"))
    )
    (net (code "68") (name "unconnected-(N1-PadLHDP)") (class "Default")
      (node (ref "N1") (pin "LHDP") (pinfunction "LHDP_LHDP") (pintype "bidirectional"))
    )
    (net (code "69") (name "unconnected-(N1-PadRHDP)") (class "Default")
      (node (ref "N1") (pin "RHDP") (pinfunction "RHDP_RHDP") (pintype "bidirectional"))
    )
    (net (code "70") (name "unconnected-(N2-PadLHDP)") (class "Default")
      (node (ref "N2") (pin "LHDP") (pinfunction "LHDP_LHDP") (pintype "bidirectional"))
    )
    (net (code "71") (name "unconnected-(N2-PadRHDP)") (class "Default")
      (node (ref "N2") (pin "RHDP") (pinfunction "RHDP_RHDP") (pintype "bidirectional"))
    )
  )
)
